# Sheet1.net
KiCad netlist of a schematic drawn in Altium Designer
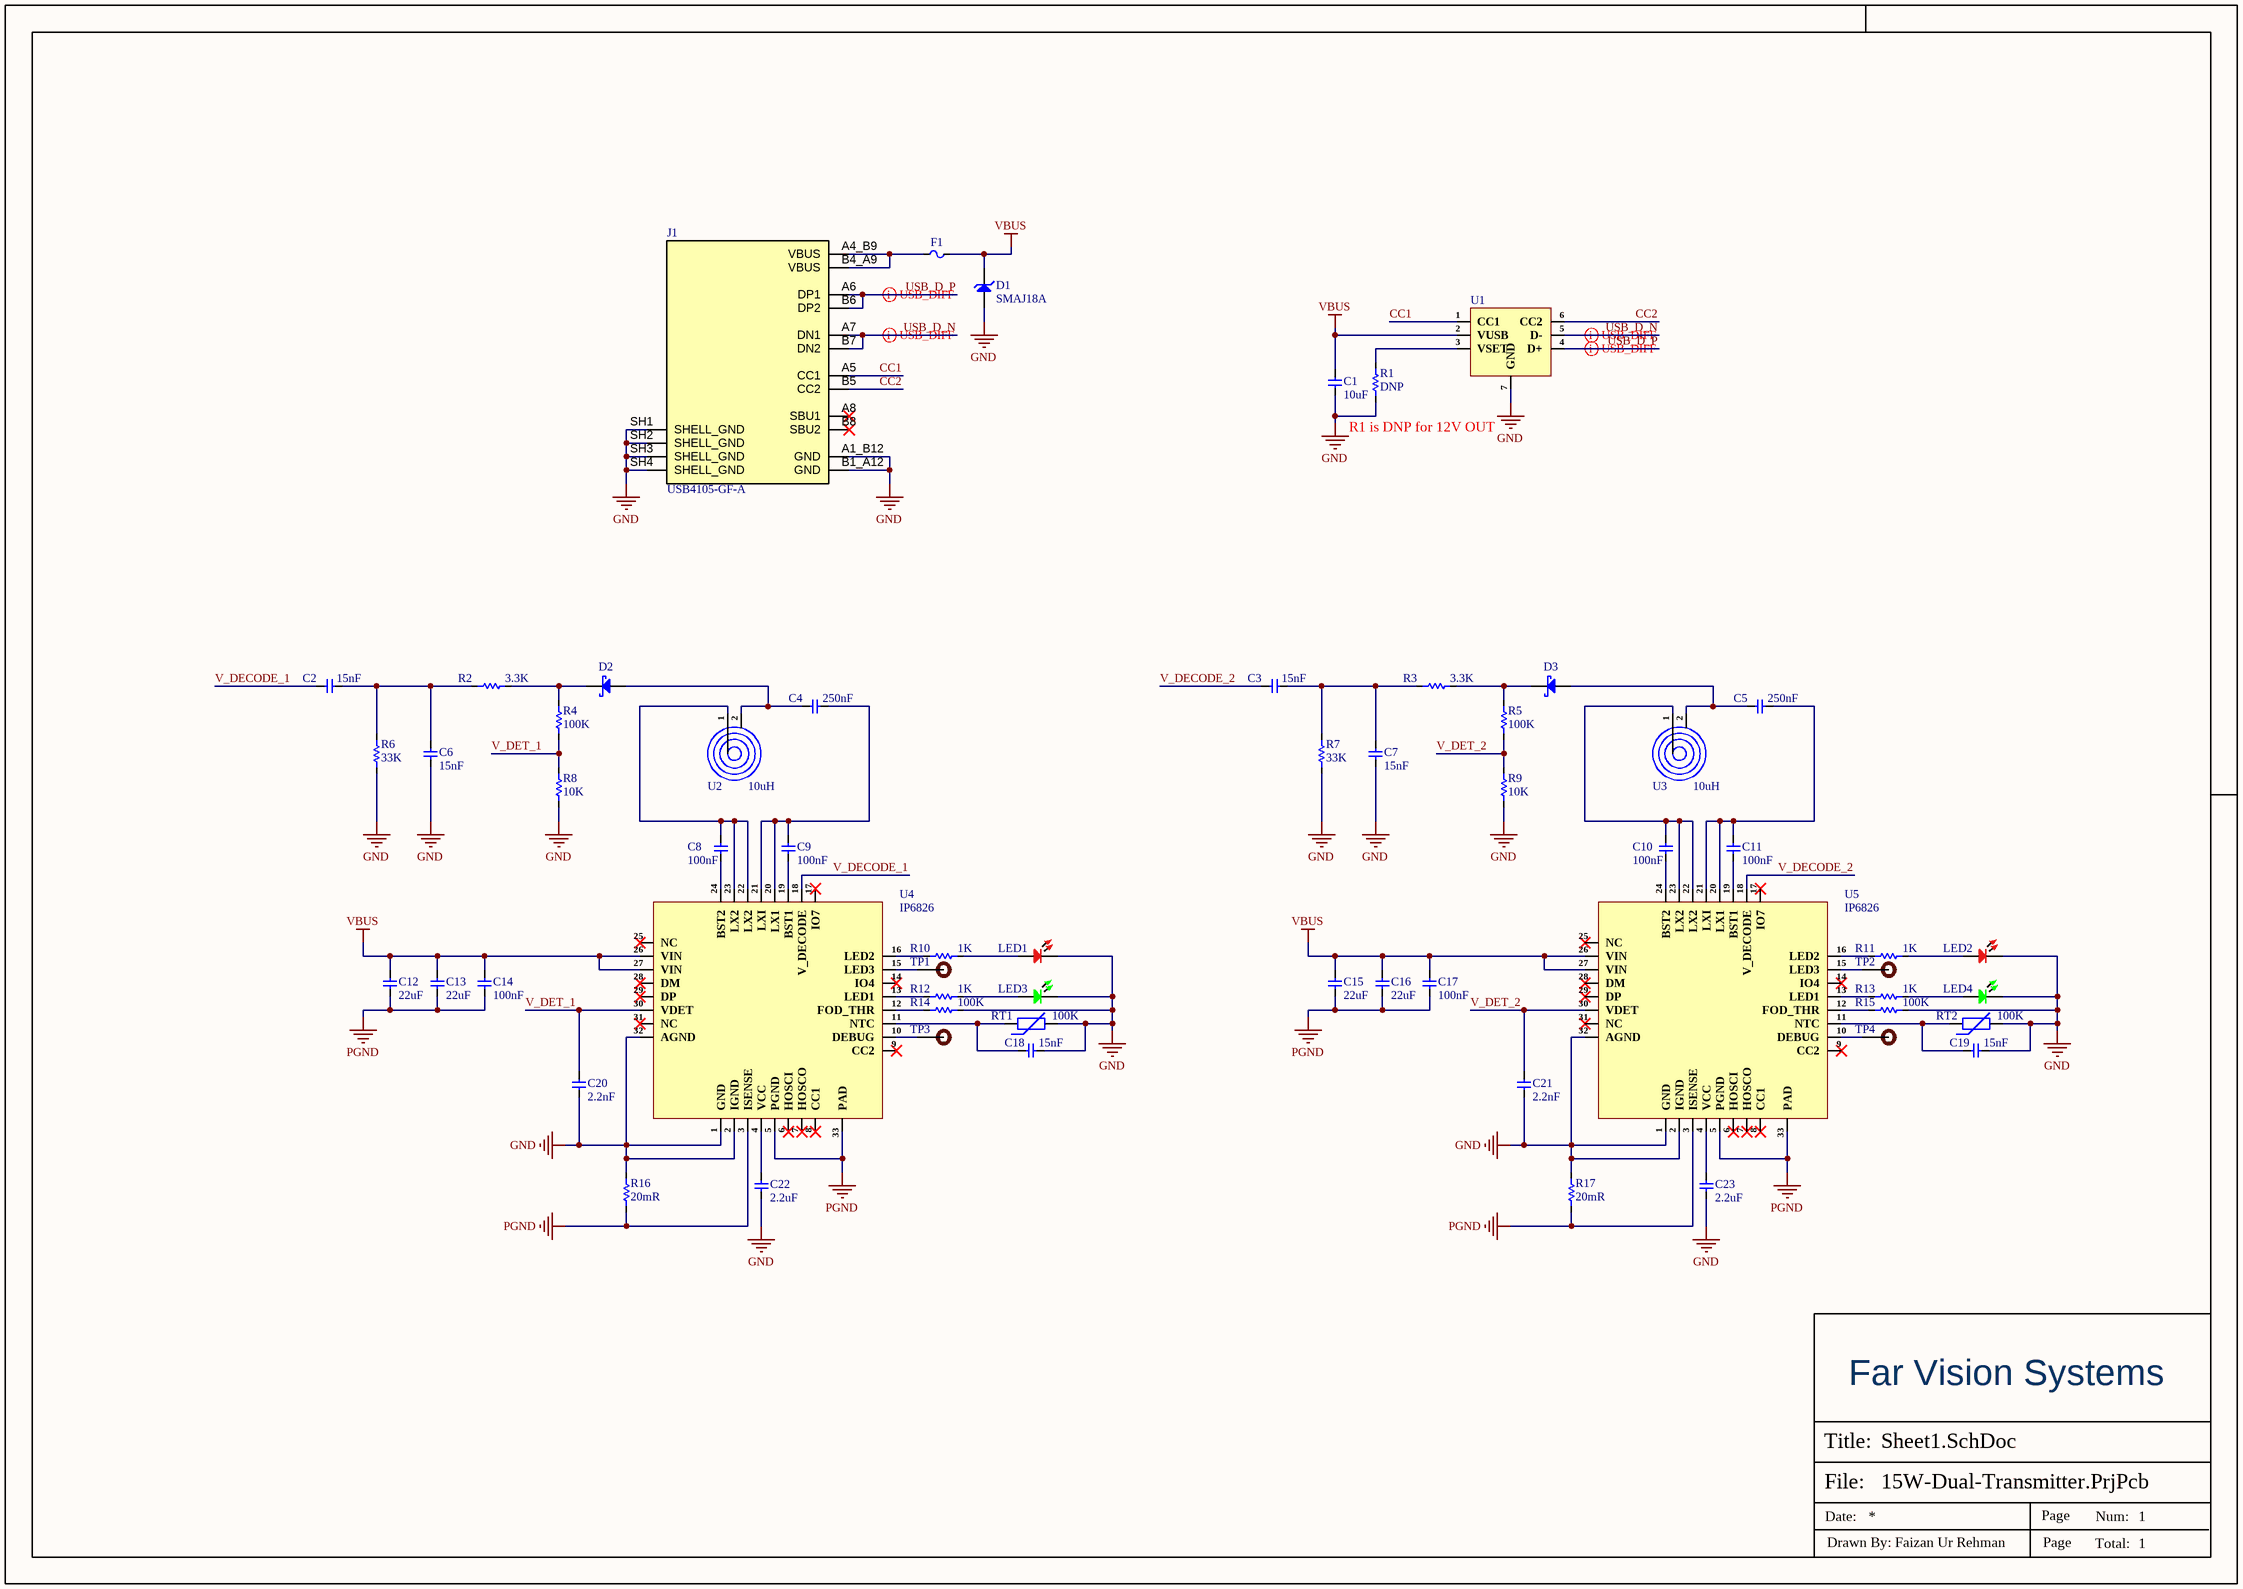
[diagram p0: Sheet1.SchDoc]

(export (version "E")
  (design (tool "Eeschema 10.0.6"))
  (components
    (comp (ref "C1")
      (value "10uF")
      (footprint "Cap-0603")
      (description "GRM188R61E106KA73D")
      (libsource (lib "Schlib1") (part "CAP-0603"))
    )
    (comp (ref "C2")
      (value "15nF")
      (footprint "Cap-0603")
      (description "CC0402KRX7R9BB153")
      (libsource (lib "Schlib1") (part "CAP-0603"))
    )
    (comp (ref "C3")
      (value "15nF")
      (footprint "Cap-0603")
      (description "CC0402KRX7R9BB153")
      (libsource (lib "Schlib1") (part "CAP-0603"))
    )
    (comp (ref "C4")
      (value "250nF")
      (footprint "CAP-TH_L9.0-W3.5-P7.50-D1.0")
      (libsource (lib "Schlib1") (part "MPP254J2A0701"))
    )
    (comp (ref "C5")
      (value "250nF")
      (footprint "CAP-TH_L9.0-W3.5-P7.50-D1.0")
      (libsource (lib "Schlib1") (part "MPP254J2A0701"))
    )
    (comp (ref "C6")
      (value "15nF")
      (footprint "Cap-0603")
      (description "CC0402KRX7R9BB153")
      (libsource (lib "Schlib1") (part "CAP-0603"))
    )
    (comp (ref "C7")
      (value "15nF")
      (footprint "Cap-0603")
      (description "CC0402KRX7R9BB153")
      (libsource (lib "Schlib1") (part "CAP-0603"))
    )
    (comp (ref "C8")
      (value "100nF")
      (footprint "Cap-0603")
      (description "GRM188R71H104KA93D")
      (libsource (lib "Schlib1") (part "CAP-0603"))
    )
    (comp (ref "C9")
      (value "100nF")
      (footprint "Cap-0603")
      (description "GRM188R71H104KA93D")
      (libsource (lib "Schlib1") (part "CAP-0603"))
    )
    (comp (ref "C10")
      (value "100nF")
      (footprint "Cap-0603")
      (description "GRM188R71H104KA93D")
      (libsource (lib "Schlib1") (part "CAP-0603"))
    )
    (comp (ref "C11")
      (value "100nF")
      (footprint "Cap-0603")
      (description "GRM188R71H104KA93D")
      (libsource (lib "Schlib1") (part "CAP-0603"))
    )
    (comp (ref "C12")
      (value "22uF")
      (footprint "Cap-0805")
      (description "CC0805MKX5R8BB226")
      (libsource (lib "Schlib1") (part "CAP-0805"))
    )
    (comp (ref "C13")
      (value "22uF")
      (footprint "Cap-0805")
      (description "CC0805MKX5R8BB226")
      (libsource (lib "Schlib1") (part "CAP-0805"))
    )
    (comp (ref "C14")
      (value "100nF")
      (footprint "Cap-0603")
      (description "GRM188R71H104KA93D")
      (libsource (lib "Schlib1") (part "CAP-0603"))
    )
    (comp (ref "C15")
      (value "22uF")
      (footprint "Cap-0805")
      (description "CC0805MKX5R8BB226")
      (libsource (lib "Schlib1") (part "CAP-0805"))
    )
    (comp (ref "C16")
      (value "22uF")
      (footprint "Cap-0805")
      (description "CC0805MKX5R8BB226")
      (libsource (lib "Schlib1") (part "CAP-0805"))
    )
    (comp (ref "C17")
      (value "100nF")
      (footprint "Cap-0603")
      (description "GRM188R71H104KA93D")
      (libsource (lib "Schlib1") (part "CAP-0603"))
    )
    (comp (ref "C18")
      (value "15nF")
      (footprint "Cap-0603")
      (description "CC0402KRX7R9BB153")
      (libsource (lib "Schlib1") (part "CAP-0603"))
    )
    (comp (ref "C19")
      (value "15nF")
      (footprint "Cap-0603")
      (description "CC0402KRX7R9BB153")
      (libsource (lib "Schlib1") (part "CAP-0603"))
    )
    (comp (ref "C20")
      (value "2.2nF")
      (footprint "Cap-0603")
      (description "GRM188R71H222KA01D")
      (libsource (lib "Schlib1") (part "CAP-0603"))
    )
    (comp (ref "C21")
      (value "2.2nF")
      (footprint "Cap-0603")
      (description "GRM188R71H222KA01D")
      (libsource (lib "Schlib1") (part "CAP-0603"))
    )
    (comp (ref "C22")
      (value "2.2uF")
      (footprint "Cap-0603")
      (description "GRM155R61E225KE11D")
      (libsource (lib "Schlib1") (part "CAP-0603"))
    )
    (comp (ref "C23")
      (value "2.2uF")
      (footprint "Cap-0603")
      (description "GRM155R61E225KE11D")
      (libsource (lib "Schlib1") (part "CAP-0603"))
    )
    (comp (ref "D1")
      (value "SMAJ18A")
      (footprint "SMA(DO-214AC)")
      (fields (field (name "MANUFACTURER") "SMC") (field (name "LCSC PART NUMBER") "C499735"))
      (libsource (lib "Schlib1") (part "SMAJ18A"))
    )
    (comp (ref "D2")
      (value "1N5819HW-7-F")
      (footprint "SOD-123")
      (description "DIODE SCHOTTKY 40V 1A SOD123")
      (fields (field (name "MANUFACTURER") "Diodes") (field (name "LCSC PART NUMBER") "C82544"))
      (libsource (lib "Schlib1") (part "1N5819HW-7-F"))
    )
    (comp (ref "D3")
      (value "1N5819HW-7-F")
      (footprint "SOD-123")
      (description "DIODE SCHOTTKY 40V 1A SOD123")
      (fields (field (name "MANUFACTURER") "Diodes") (field (name "LCSC PART NUMBER") "C82544"))
      (libsource (lib "Schlib1") (part "1N5819HW-7-F"))
    )
    (comp (ref "F1")
      (value "BSMD1812-300-24V")
      (footprint "Fuse-1812_")
      (description "24V 3A 40A 6A 1812 Resettable Fuses ROHS")
      (fields (field (name "LCSC PART NUMBER") "C7500481") (field (name "MANUFACTURER") "BHFUSE"))
      (libsource (lib "Schlib1") (part "BSMD1812-300-24V"))
    )
    (comp (ref "J1")
      (value "USB4105-GF-A")
      (footprint "GCT_USB4105-GF-A")
      (fields (field (name "MF") "{'manufacturer': u'GCT'}"))
      (libsource (lib "Schlib1") (part "USB4105-GF-A"))
    )
    (comp (ref "LED1")
      (value "RED")
      (footprint "LED-0603")
      (description "RED LED 0603 Light Emitting Diodes")
      (fields
        (field (name "MANUFACTURER") "Foshan NationStar Optoelectronics")
        (field (name "MANUFACTURER PART NUMBER") "NCD0603R3")
      )
      (libsource (lib "Schlib1") (part "NCD0603R3"))
    )
    (comp (ref "LED2")
      (value "RED")
      (footprint "LED-0603")
      (description "RED LED 0603 Light Emitting Diodes")
      (fields
        (field (name "MANUFACTURER") "Foshan NationStar Optoelectronics")
        (field (name "MANUFACTURER PART NUMBER") "NCD0603R3")
      )
      (libsource (lib "Schlib1") (part "NCD0603R3"))
    )
    (comp (ref "LED3")
      (value "Emerald")
      (footprint "LED-0603")
      (description "Emerald 0603 Light Emitting Diodes (LED) ROHS")
      (fields
        (field (name "MANUFACTURER") "Foshan NationStar Optoelectronics")
        (field (name "MANUFACTURER PART NUMBER") "NCD0603G2")
      )
      (libsource (lib "Schlib1") (part "NCD0603G2"))
    )
    (comp (ref "LED4")
      (value "Emerald")
      (footprint "LED-0603")
      (description "Emerald 0603 Light Emitting Diodes (LED) ROHS")
      (fields
        (field (name "MANUFACTURER") "Foshan NationStar Optoelectronics")
        (field (name "MANUFACTURER PART NUMBER") "NCD0603G2")
      )
      (libsource (lib "Schlib1") (part "NCD0603G2"))
    )
    (comp (ref "R1") (value "DNP") (footprint "Res-0603") (libsource (lib "Schlib1") (part "RES-0603")))
    (comp (ref "R2")
      (value "3.3K")
      (footprint "Res-0603")
      (description "RC0603FR-073K3L")
      (libsource (lib "Schlib1") (part "RES-0603"))
    )
    (comp (ref "R3")
      (value "3.3K")
      (footprint "Res-0603")
      (description "RC0603FR-073K3L")
      (libsource (lib "Schlib1") (part "RES-0603"))
    )
    (comp (ref "R4")
      (value "100K")
      (footprint "Res-0603")
      (description "RT0603BRD07100KL")
      (libsource (lib "Schlib1") (part "RES-0603"))
    )
    (comp (ref "R5")
      (value "100K")
      (footprint "Res-0603")
      (description "RT0603BRD07100KL")
      (libsource (lib "Schlib1") (part "RES-0603"))
    )
    (comp (ref "R6")
      (value "33K")
      (footprint "Res-0603")
      (description "RC0603FR-0733KL")
      (libsource (lib "Schlib1") (part "RES-0603"))
    )
    (comp (ref "R7")
      (value "33K")
      (footprint "Res-0603")
      (description "RC0603FR-0733KL")
      (libsource (lib "Schlib1") (part "RES-0603"))
    )
    (comp (ref "R8")
      (value "10K")
      (footprint "Res-0603")
      (description "RC0603FR-0710KL")
      (libsource (lib "Schlib1") (part "RES-0603"))
    )
    (comp (ref "R9")
      (value "10K")
      (footprint "Res-0603")
      (description "RC0603FR-0710KL")
      (libsource (lib "Schlib1") (part "RES-0603"))
    )
    (comp (ref "R10")
      (value "1K")
      (footprint "Res-0603")
      (description "RC0603FR-071KL")
      (libsource (lib "Schlib1") (part "RES-0603"))
    )
    (comp (ref "R11")
      (value "1K")
      (footprint "Res-0603")
      (description "RC0603FR-071KL")
      (libsource (lib "Schlib1") (part "RES-0603"))
    )
    (comp (ref "R12") (value "1K") (footprint "Res-0603") (libsource (lib "Schlib1") (part "RES-0603")))
    (comp (ref "R13") (value "1K") (footprint "Res-0603") (libsource (lib "Schlib1") (part "RES-0603")))
    (comp (ref "R14")
      (value "100K")
      (footprint "Res-0603")
      (description "RT0603BRD07100KL")
      (libsource (lib "Schlib1") (part "RES-0603"))
    )
    (comp (ref "R15")
      (value "100K")
      (footprint "Res-0603")
      (description "RT0603BRD07100KL")
      (libsource (lib "Schlib1") (part "RES-0603"))
    )
    (comp (ref "R16")
      (value "20mR")
      (footprint "RES-2512")
      (description "RES 0.02 OHM 1% 2W 2512")
      (fields (field (name "LCSC PART NUMBER") "C375689") (field (name "MANUFACTURER") "Yageo"))
      (libsource (lib "Schlib1") (part "PA2512FKE7W0R02E"))
    )
    (comp (ref "R17")
      (value "20mR")
      (footprint "RES-2512")
      (description "RES 0.02 OHM 1% 2W 2512")
      (fields (field (name "LCSC PART NUMBER") "C375689") (field (name "MANUFACTURER") "Yageo"))
      (libsource (lib "Schlib1") (part "PA2512FKE7W0R02E"))
    )
    (comp (ref "RT1")
      (value "100K")
      (footprint "Res-0603")
      (description "100kΩ 100uA 100mW 3950K ±1% 0603 NTC Thermistors ROHS")
      (fields
        (field (name "MANUFACTURER") "KUU")
        (field (name "MANUFACTURER PART NUMBER") "KNTC0603/100KF3950")
      )
      (libsource (lib "Schlib1") (part "KNTC0603/100KF3950"))
    )
    (comp (ref "RT2")
      (value "100K")
      (footprint "Res-0603")
      (description "100kΩ 100uA 100mW 3950K ±1% 0603 NTC Thermistors ROHS")
      (fields
        (field (name "MANUFACTURER") "KUU")
        (field (name "MANUFACTURER PART NUMBER") "KNTC0603/100KF3950")
      )
      (libsource (lib "Schlib1") (part "KNTC0603/100KF3950"))
    )
    (comp (ref "TP1")
      (value "TEST POINT")
      (footprint "Test-point")
      (description "Test Point ON")
      (libsource (lib "Schlib1") (part "TEST POINT"))
    )
    (comp (ref "TP2")
      (value "TEST POINT")
      (footprint "Test-point")
      (description "Test Point ON")
      (libsource (lib "Schlib1") (part "TEST POINT"))
    )
    (comp (ref "TP3")
      (value "TEST POINT")
      (footprint "Test-point")
      (description "Test Point ON")
      (libsource (lib "Schlib1") (part "TEST POINT"))
    )
    (comp (ref "TP4")
      (value "TEST POINT")
      (footprint "Test-point")
      (description "Test Point ON")
      (libsource (lib "Schlib1") (part "TEST POINT"))
    )
    (comp (ref "U1")
      (value "HUSB237-AA001-DN06R")
      (footprint "DFN-6L-EP(2x2)")
      (description "DFN-6L-EP(2x2) USB PD ROHS")
      (fields (field (name "MANUFACTURER") "Hynetek") (field (name "LCSC PART NUMBER") "C22373734"))
      (libsource (lib "Schlib1") (part "HUSB237-AA001-DN06R"))
    )
    (comp (ref "U2")
      (value "10uH")
      (footprint "760308103102")
      (description "WE-WPCC Wireless Power Transfer Transmitter Coil, THT, Qi - MP-A2, 10uH, 150W")
      (fields
        (field (name "MANUFACTURER PART NUMBER") "760308103102")
        (field (name "MANUFACTURER") "Wurth Elektronik")
      )
      (libsource (lib "Schlib1") (part "760308103102"))
    )
    (comp (ref "U3")
      (value "10uH")
      (footprint "760308103102")
      (description "WE-WPCC Wireless Power Transfer Transmitter Coil, THT, Qi - MP-A2, 10uH, 150W")
      (fields
        (field (name "MANUFACTURER PART NUMBER") "760308103102")
        (field (name "MANUFACTURER") "Wurth Elektronik")
      )
      (libsource (lib "Schlib1") (part "760308103102"))
    )
    (comp (ref "U4")
      (value "IP6826")
      (footprint "QFN-32_L5.0-W5.0-P0.50-BL-EP3.8")
      (libsource (lib "Schlib1") (part "IP6826"))
    )
    (comp (ref "U5")
      (value "IP6826")
      (footprint "QFN-32_L5.0-W5.0-P0.50-BL-EP3.8")
      (libsource (lib "Schlib1") (part "IP6826"))
    )
  )
  (nets
    (net (code "1") (name "/CC1") (class "Default")
      (node (ref "J1") (pin "A5") (pinfunction "CC1_A5") (pintype "passive"))
      (node (ref "U1") (pin "1") (pinfunction "CC1_1") (pintype "passive"))
    )
    (net (code "2") (name "/CC2") (class "Default")
      (node (ref "J1") (pin "B5") (pinfunction "CC2_B5") (pintype "passive"))
      (node (ref "U1") (pin "6") (pinfunction "CC2_6") (pintype "passive"))
    )
    (net (code "3") (name "/USB_D_N") (class "Default")
      (node (ref "J1") (pin "A7") (pinfunction "DN1_A7") (pintype "passive"))
      (node (ref "J1") (pin "B7") (pinfunction "DN2_B7") (pintype "passive"))
      (node (ref "U1") (pin "5") (pinfunction "D-_5") (pintype "passive"))
    )
    (net (code "4") (name "/USB_D_P") (class "Default")
      (node (ref "J1") (pin "A6") (pinfunction "DP1_A6") (pintype "passive"))
      (node (ref "J1") (pin "B6") (pinfunction "DP2_B6") (pintype "passive"))
      (node (ref "U1") (pin "4") (pinfunction "D+_4") (pintype "passive"))
    )
    (net (code "5") (name "/V_DECODE_1") (class "Default")
      (node (ref "C2") (pin "2") (pinfunction "2_2") (pintype "passive"))
      (node (ref "U4") (pin "18") (pinfunction "V_DECODE_18") (pintype "passive"))
    )
    (net (code "6") (name "/V_DECODE_2") (class "Default")
      (node (ref "C3") (pin "2") (pinfunction "2_2") (pintype "passive"))
      (node (ref "U5") (pin "18") (pinfunction "V_DECODE_18") (pintype "passive"))
    )
    (net (code "7") (name "/V_DET_1") (class "Default")
      (node (ref "C20") (pin "2") (pinfunction "2_2") (pintype "passive"))
      (node (ref "R4") (pin "1") (pinfunction "1_1") (pintype "passive"))
      (node (ref "R8") (pin "2") (pinfunction "2_2") (pintype "passive"))
      (node (ref "U4") (pin "30") (pinfunction "VDET_30") (pintype "passive"))
    )
    (net (code "8") (name "/V_DET_2") (class "Default")
      (node (ref "C21") (pin "2") (pinfunction "2_2") (pintype "passive"))
      (node (ref "R5") (pin "1") (pinfunction "1_1") (pintype "passive"))
      (node (ref "R9") (pin "2") (pinfunction "2_2") (pintype "passive"))
      (node (ref "U5") (pin "30") (pinfunction "VDET_30") (pintype "passive"))
    )
    (net (code "9") (name "GND") (class "Default")
      (node (ref "C1") (pin "1") (pinfunction "1_1") (pintype "passive"))
      (node (ref "C18") (pin "2") (pinfunction "2_2") (pintype "passive"))
      (node (ref "C19") (pin "2") (pinfunction "2_2") (pintype "passive"))
      (node (ref "C20") (pin "1") (pinfunction "1_1") (pintype "passive"))
      (node (ref "C21") (pin "1") (pinfunction "1_1") (pintype "passive"))
      (node (ref "C22") (pin "1") (pinfunction "1_1") (pintype "passive"))
      (node (ref "C23") (pin "1") (pinfunction "1_1") (pintype "passive"))
      (node (ref "C6") (pin "1") (pinfunction "1_1") (pintype "passive"))
      (node (ref "C7") (pin "1") (pinfunction "1_1") (pintype "passive"))
      (node (ref "D1") (pin "2") (pinfunction "A_2") (pintype "passive"))
      (node (ref "J1") (pin "A1_B12") (pinfunction "GND_A1_B12") (pintype "passive"))
      (node (ref "J1") (pin "B1_A12") (pinfunction "GND_B1_A12") (pintype "passive"))
      (node (ref "J1") (pin "SH1") (pinfunction "SHELL_GND_SH1") (pintype "passive"))
      (node (ref "J1") (pin "SH2") (pinfunction "SHELL_GND_SH2") (pintype "passive"))
      (node (ref "J1") (pin "SH3") (pinfunction "SHELL_GND_SH3") (pintype "passive"))
      (node (ref "J1") (pin "SH4") (pinfunction "SHELL_GND_SH4") (pintype "passive"))
      (node (ref "LED1") (pin "2") (pinfunction "2_2") (pintype "passive"))
      (node (ref "LED2") (pin "2") (pinfunction "2_2") (pintype "passive"))
      (node (ref "LED3") (pin "2") (pinfunction "2_2") (pintype "passive"))
      (node (ref "LED4") (pin "2") (pinfunction "2_2") (pintype "passive"))
      (node (ref "R1") (pin "1") (pinfunction "1_1") (pintype "passive"))
      (node (ref "R14") (pin "2") (pinfunction "2_2") (pintype "passive"))
      (node (ref "R15") (pin "2") (pinfunction "2_2") (pintype "passive"))
      (node (ref "R16") (pin "2") (pinfunction "2_2") (pintype "passive"))
      (node (ref "R17") (pin "2") (pinfunction "2_2") (pintype "passive"))
      (node (ref "R6") (pin "1") (pinfunction "1_1") (pintype "passive"))
      (node (ref "R7") (pin "1") (pinfunction "1_1") (pintype "passive"))
      (node (ref "R8") (pin "1") (pinfunction "1_1") (pintype "passive"))
      (node (ref "R9") (pin "1") (pinfunction "1_1") (pintype "passive"))
      (node (ref "RT1") (pin "2") (pinfunction "2_2") (pintype "passive"))
      (node (ref "RT2") (pin "2") (pinfunction "2_2") (pintype "passive"))
      (node (ref "U1") (pin "7") (pinfunction "GND_7") (pintype "passive"))
      (node (ref "U4") (pin "1") (pinfunction "GND_1") (pintype "passive"))
      (node (ref "U4") (pin "2") (pinfunction "IGND_2") (pintype "passive"))
      (node (ref "U4") (pin "32") (pinfunction "AGND_32") (pintype "passive"))
      (node (ref "U5") (pin "1") (pinfunction "GND_1") (pintype "passive"))
      (node (ref "U5") (pin "2") (pinfunction "IGND_2") (pintype "passive"))
      (node (ref "U5") (pin "32") (pinfunction "AGND_32") (pintype "passive"))
    )
    (net (code "10") (name "Net-(C2-Pad1)") (class "Default")
      (node (ref "C2") (pin "1") (pinfunction "1_1") (pintype "passive"))
      (node (ref "C6") (pin "2") (pinfunction "2_2") (pintype "passive"))
      (node (ref "R2") (pin "1") (pinfunction "1_1") (pintype "passive"))
      (node (ref "R6") (pin "2") (pinfunction "2_2") (pintype "passive"))
    )
    (net (code "11") (name "Net-(C3-Pad1)") (class "Default")
      (node (ref "C3") (pin "1") (pinfunction "1_1") (pintype "passive"))
      (node (ref "C7") (pin "2") (pinfunction "2_2") (pintype "passive"))
      (node (ref "R3") (pin "1") (pinfunction "1_1") (pintype "passive"))
      (node (ref "R7") (pin "2") (pinfunction "2_2") (pintype "passive"))
    )
    (net (code "12") (name "Net-(C8-Pad2)") (class "Default")
      (node (ref "C8") (pin "2") (pinfunction "2_2") (pintype "passive"))
      (node (ref "U2") (pin "1") (pinfunction "1_1") (pintype "passive"))
      (node (ref "U4") (pin "22") (pinfunction "LX2_22") (pintype "passive"))
      (node (ref "U4") (pin "23") (pinfunction "LX2_23") (pintype "passive"))
    )
    (net (code "13") (name "Net-(C10-Pad2)") (class "Default")
      (node (ref "C10") (pin "2") (pinfunction "2_2") (pintype "passive"))
      (node (ref "U3") (pin "1") (pinfunction "1_1") (pintype "passive"))
      (node (ref "U5") (pin "22") (pinfunction "LX2_22") (pintype "passive"))
      (node (ref "U5") (pin "23") (pinfunction "LX2_23") (pintype "passive"))
    )
    (net (code "14") (name "Net-(D2-A)") (class "Default")
      (node (ref "C4") (pin "1") (pinfunction "1_1") (pintype "passive"))
      (node (ref "D2") (pin "1") (pinfunction "A_1") (pintype "passive"))
      (node (ref "U2") (pin "2") (pinfunction "2_2") (pintype "passive"))
    )
    (net (code "15") (name "Net-(D2-K)") (class "Default")
      (node (ref "D2") (pin "2") (pinfunction "K_2") (pintype "passive"))
      (node (ref "R2") (pin "2") (pinfunction "2_2") (pintype "passive"))
      (node (ref "R4") (pin "2") (pinfunction "2_2") (pintype "passive"))
    )
    (net (code "16") (name "Net-(D3-A)") (class "Default")
      (node (ref "C5") (pin "1") (pinfunction "1_1") (pintype "passive"))
      (node (ref "D3") (pin "1") (pinfunction "A_1") (pintype "passive"))
      (node (ref "U3") (pin "2") (pinfunction "2_2") (pintype "passive"))
    )
    (net (code "17") (name "Net-(D3-K)") (class "Default")
      (node (ref "D3") (pin "2") (pinfunction "K_2") (pintype "passive"))
      (node (ref "R3") (pin "2") (pinfunction "2_2") (pintype "passive"))
      (node (ref "R5") (pin "2") (pinfunction "2_2") (pintype "passive"))
    )
    (net (code "18") (name "Net-(F1-Pad1)") (class "Default")
      (node (ref "F1") (pin "1") (pinfunction "1_1") (pintype "passive"))
      (node (ref "J1") (pin "A4_B9") (pinfunction "VBUS_A4_B9") (pintype "passive"))
      (node (ref "J1") (pin "B4_A9") (pinfunction "VBUS_B4_A9") (pintype "passive"))
    )
    (net (code "19") (name "Net-(LED1-Pad1)") (class "Default")
      (node (ref "LED1") (pin "1") (pinfunction "1_1") (pintype "passive"))
      (node (ref "R10") (pin "2") (pinfunction "2_2") (pintype "passive"))
    )
    (net (code "20") (name "Net-(LED2-Pad1)") (class "Default")
      (node (ref "LED2") (pin "1") (pinfunction "1_1") (pintype "passive"))
      (node (ref "R11") (pin "2") (pinfunction "2_2") (pintype "passive"))
    )
    (net (code "21") (name "Net-(LED3-Pad1)") (class "Default")
      (node (ref "LED3") (pin "1") (pinfunction "1_1") (pintype "passive"))
      (node (ref "R12") (pin "2") (pinfunction "2_2") (pintype "passive"))
    )
    (net (code "22") (name "Net-(LED4-Pad1)") (class "Default")
      (node (ref "LED4") (pin "1") (pinfunction "1_1") (pintype "passive"))
      (node (ref "R13") (pin "2") (pinfunction "2_2") (pintype "passive"))
    )
    (net (code "23") (name "Net-(U1-VSET)") (class "Default")
      (node (ref "R1") (pin "2") (pinfunction "2_2") (pintype "passive"))
      (node (ref "U1") (pin "3") (pinfunction "VSET_3") (pintype "passive"))
    )
    (net (code "24") (name "Net-(U4-BST1)") (class "Default")
      (node (ref "C9") (pin "1") (pinfunction "1_1") (pintype "passive"))
      (node (ref "U4") (pin "19") (pinfunction "BST1_19") (pintype "passive"))
    )
    (net (code "25") (name "Net-(U4-BST2)") (class "Default")
      (node (ref "C8") (pin "1") (pinfunction "1_1") (pintype "passive"))
      (node (ref "U4") (pin "24") (pinfunction "BST2_24") (pintype "passive"))
    )
    (net (code "26") (name "Net-(U4-DEBUG)") (class "Default")
      (node (ref "TP3") (pin "1") (pinfunction "1_1") (pintype "passive"))
      (node (ref "U4") (pin "10") (pinfunction "DEBUG_10") (pintype "passive"))
    )
    (net (code "27") (name "Net-(U4-FOD_THR)") (class "Default")
      (node (ref "R14") (pin "1") (pinfunction "1_1") (pintype "passive"))
      (node (ref "U4") (pin "12") (pinfunction "FOD_THR_12") (pintype "passive"))
    )
    (net (code "28") (name "Net-(U4-LED1)") (class "Default")
      (node (ref "R12") (pin "1") (pinfunction "1_1") (pintype "passive"))
      (node (ref "U4") (pin "13") (pinfunction "LED1_13") (pintype "passive"))
    )
    (net (code "29") (name "Net-(U4-LED2)") (class "Default")
      (node (ref "R10") (pin "1") (pinfunction "1_1") (pintype "passive"))
      (node (ref "U4") (pin "16") (pinfunction "LED2_16") (pintype "passive"))
    )
    (net (code "30") (name "Net-(U4-LED3)") (class "Default")
      (node (ref "TP1") (pin "1") (pinfunction "1_1") (pintype "passive"))
      (node (ref "U4") (pin "15") (pinfunction "LED3_15") (pintype "passive"))
    )
    (net (code "31") (name "Net-(U4-LX1)") (class "Default")
      (node (ref "C4") (pin "2") (pinfunction "2_2") (pintype "passive"))
      (node (ref "C9") (pin "2") (pinfunction "2_2") (pintype "passive"))
      (node (ref "U4") (pin "20") (pinfunction "LX1_20") (pintype "passive"))
      (node (ref "U4") (pin "21") (pinfunction "LXI_21") (pintype "passive"))
    )
    (net (code "32") (name "Net-(U4-NTC)") (class "Default")
      (node (ref "C18") (pin "1") (pinfunction "1_1") (pintype "passive"))
      (node (ref "RT1") (pin "1") (pinfunction "1_1") (pintype "passive"))
      (node (ref "U4") (pin "11") (pinfunction "NTC_11") (pintype "passive"))
    )
    (net (code "33") (name "Net-(U4-VCC)") (class "Default")
      (node (ref "C22") (pin "2") (pinfunction "2_2") (pintype "passive"))
      (node (ref "U4") (pin "4") (pinfunction "VCC_4") (pintype "passive"))
    )
    (net (code "34") (name "Net-(U5-BST1)") (class "Default")
      (node (ref "C11") (pin "1") (pinfunction "1_1") (pintype "passive"))
      (node (ref "U5") (pin "19") (pinfunction "BST1_19") (pintype "passive"))
    )
    (net (code "35") (name "Net-(U5-BST2)") (class "Default")
      (node (ref "C10") (pin "1") (pinfunction "1_1") (pintype "passive"))
      (node (ref "U5") (pin "24") (pinfunction "BST2_24") (pintype "passive"))
    )
    (net (code "36") (name "Net-(U5-DEBUG)") (class "Default")
      (node (ref "TP4") (pin "1") (pinfunction "1_1") (pintype "passive"))
      (node (ref "U5") (pin "10") (pinfunction "DEBUG_10") (pintype "passive"))
    )
    (net (code "37") (name "Net-(U5-FOD_THR)") (class "Default")
      (node (ref "R15") (pin "1") (pinfunction "1_1") (pintype "passive"))
      (node (ref "U5") (pin "12") (pinfunction "FOD_THR_12") (pintype "passive"))
    )
    (net (code "38") (name "Net-(U5-LED1)") (class "Default")
      (node (ref "R13") (pin "1") (pinfunction "1_1") (pintype "passive"))
      (node (ref "U5") (pin "13") (pinfunction "LED1_13") (pintype "passive"))
    )
    (net (code "39") (name "Net-(U5-LED2)") (class "Default")
      (node (ref "R11") (pin "1") (pinfunction "1_1") (pintype "passive"))
      (node (ref "U5") (pin "16") (pinfunction "LED2_16") (pintype "passive"))
    )
    (net (code "40") (name "Net-(U5-LED3)") (class "Default")
      (node (ref "TP2") (pin "1") (pinfunction "1_1") (pintype "passive"))
      (node (ref "U5") (pin "15") (pinfunction "LED3_15") (pintype "passive"))
    )
    (net (code "41") (name "Net-(U5-LX1)") (class "Default")
      (node (ref "C11") (pin "2") (pinfunction "2_2") (pintype "passive"))
      (node (ref "C5") (pin "2") (pinfunction "2_2") (pintype "passive"))
      (node (ref "U5") (pin "20") (pinfunction "LX1_20") (pintype "passive"))
      (node (ref "U5") (pin "21") (pinfunction "LXI_21") (pintype "passive"))
    )
    (net (code "42") (name "Net-(U5-NTC)") (class "Default")
      (node (ref "C19") (pin "1") (pinfunction "1_1") (pintype "passive"))
      (node (ref "RT2") (pin "1") (pinfunction "1_1") (pintype "passive"))
      (node (ref "U5") (pin "11") (pinfunction "NTC_11") (pintype "passive"))
    )
    (net (code "43") (name "Net-(U5-VCC)") (class "Default")
      (node (ref "C23") (pin "2") (pinfunction "2_2") (pintype "passive"))
      (node (ref "U5") (pin "4") (pinfunction "VCC_4") (pintype "passive"))
    )
    (net (code "44") (name "PGND") (class "Default")
      (node (ref "C12") (pin "1") (pinfunction "1_1") (pintype "passive"))
      (node (ref "C13") (pin "1") (pinfunction "1_1") (pintype "passive"))
      (node (ref "C14") (pin "1") (pinfunction "1_1") (pintype "passive"))
      (node (ref "C15") (pin "1") (pinfunction "1_1") (pintype "passive"))
      (node (ref "C16") (pin "1") (pinfunction "1_1") (pintype "passive"))
      (node (ref "C17") (pin "1") (pinfunction "1_1") (pintype "passive"))
      (node (ref "R16") (pin "1") (pinfunction "1_1") (pintype "passive"))
      (node (ref "R17") (pin "1") (pinfunction "1_1") (pintype "passive"))
      (node (ref "U4") (pin "3") (pinfunction "ISENSE_3") (pintype "passive"))
      (node (ref "U4") (pin "33") (pinfunction "PAD_33") (pintype "passive"))
      (node (ref "U4") (pin "5") (pinfunction "PGND_5") (pintype "passive"))
      (node (ref "U5") (pin "3") (pinfunction "ISENSE_3") (pintype "passive"))
      (node (ref "U5") (pin "33") (pinfunction "PAD_33") (pintype "passive"))
      (node (ref "U5") (pin "5") (pinfunction "PGND_5") (pintype "passive"))
    )
    (net (code "45") (name "VBUS") (class "Default")
      (node (ref "C1") (pin "2") (pinfunction "2_2") (pintype "passive"))
      (node (ref "C12") (pin "2") (pinfunction "2_2") (pintype "passive"))
      (node (ref "C13") (pin "2") (pinfunction "2_2") (pintype "passive"))
      (node (ref "C14") (pin "2") (pinfunction "2_2") (pintype "passive"))
      (node (ref "C15") (pin "2") (pinfunction "2_2") (pintype "passive"))
      (node (ref "C16") (pin "2") (pinfunction "2_2") (pintype "passive"))
      (node (ref "C17") (pin "2") (pinfunction "2_2") (pintype "passive"))
      (node (ref "D1") (pin "1") (pinfunction "K_1") (pintype "passive"))
      (node (ref "F1") (pin "2") (pinfunction "2_2") (pintype "passive"))
      (node (ref "U1") (pin "2") (pinfunction "VUSB_2") (pintype "passive"))
      (node (ref "U4") (pin "26") (pinfunction "VIN_26") (pintype "passive"))
      (node (ref "U4") (pin "27") (pinfunction "VIN_27") (pintype "passive"))
      (node (ref "U5") (pin "26") (pinfunction "VIN_26") (pintype "passive"))
      (node (ref "U5") (pin "27") (pinfunction "VIN_27") (pintype "passive"))
    )
    (net (code "46") (name "unconnected-(J1-SBU1-PadA8)") (class "Default")
      (node (ref "J1") (pin "A8") (pinfunction "SBU1_A8") (pintype "passive+no_connect"))
    )
    (net (code "47") (name "unconnected-(J1-SBU2-PadB8)") (class "Default")
      (node (ref "J1") (pin "B8") (pinfunction "SBU2_B8") (pintype "passive+no_connect"))
    )
    (net (code "48") (name "unconnected-(U4-CC1-Pad8)") (class "Default")
      (node (ref "U4") (pin "8") (pinfunction "CC1_8") (pintype "passive+no_connect"))
    )
    (net (code "49") (name "unconnected-(U4-CC2-Pad9)") (class "Default")
      (node (ref "U4") (pin "9") (pinfunction "CC2_9") (pintype "passive+no_connect"))
    )
    (net (code "50") (name "unconnected-(U4-DM-Pad28)") (class "Default")
      (node (ref "U4") (pin "28") (pinfunction "DM_28") (pintype "passive+no_connect"))
    )
    (net (code "51") (name "unconnected-(U4-DP-Pad29)") (class "Default")
      (node (ref "U4") (pin "29") (pinfunction "DP_29") (pintype "passive+no_connect"))
    )
    (net (code "52") (name "unconnected-(U4-HOSCI-Pad6)") (class "Default")
      (node (ref "U4") (pin "6") (pinfunction "HOSCI_6") (pintype "passive+no_connect"))
    )
    (net (code "53") (name "unconnected-(U4-HOSCO-Pad7)") (class "Default")
      (node (ref "U4") (pin "7") (pinfunction "HOSCO_7") (pintype "passive+no_connect"))
    )
    (net (code "54") (name "unconnected-(U4-IO4-Pad14)") (class "Default")
      (node (ref "U4") (pin "14") (pinfunction "IO4_14") (pintype "passive+no_connect"))
    )
    (net (code "55") (name "unconnected-(U4-IO7-Pad17)") (class "Default")
      (node (ref "U4") (pin "17") (pinfunction "IO7_17") (pintype "passive+no_connect"))
    )
    (net (code "56") (name "unconnected-(U4-NC-Pad25)") (class "Default")
      (node (ref "U4") (pin "25") (pinfunction "NC_25") (pintype "passive+no_connect"))
    )
    (net (code "57") (name "unconnected-(U4-NC-Pad31)") (class "Default")
      (node (ref "U4") (pin "31") (pinfunction "NC_31") (pintype "passive+no_connect"))
    )
    (net (code "58") (name "unconnected-(U5-CC1-Pad8)") (class "Default")
      (node (ref "U5") (pin "8") (pinfunction "CC1_8") (pintype "passive+no_connect"))
    )
    (net (code "59") (name "unconnected-(U5-CC2-Pad9)") (class "Default")
      (node (ref "U5") (pin "9") (pinfunction "CC2_9") (pintype "passive+no_connect"))
    )
    (net (code "60") (name "unconnected-(U5-DM-Pad28)") (class "Default")
      (node (ref "U5") (pin "28") (pinfunction "DM_28") (pintype "passive+no_connect"))
    )
    (net (code "61") (name "unconnected-(U5-DP-Pad29)") (class "Default")
      (node (ref "U5") (pin "29") (pinfunction "DP_29") (pintype "passive+no_connect"))
    )
    (net (code "62") (name "unconnected-(U5-HOSCI-Pad6)") (class "Default")
      (node (ref "U5") (pin "6") (pinfunction "HOSCI_6") (pintype "passive+no_connect"))
    )
    (net (code "63") (name "unconnected-(U5-HOSCO-Pad7)") (class "Default")
      (node (ref "U5") (pin "7") (pinfunction "HOSCO_7") (pintype "passive+no_connect"))
    )
    (net (code "64") (name "unconnected-(U5-IO4-Pad14)") (class "Default")
      (node (ref "U5") (pin "14") (pinfunction "IO4_14") (pintype "passive+no_connect"))
    )
    (net (code "65") (name "unconnected-(U5-IO7-Pad17)") (class "Default")
      (node (ref "U5") (pin "17") (pinfunction "IO7_17") (pintype "passive+no_connect"))
    )
    (net (code "66") (name "unconnected-(U5-NC-Pad25)") (class "Default")
      (node (ref "U5") (pin "25") (pinfunction "NC_25") (pintype "passive+no_connect"))
    )
    (net (code "67") (name "unconnected-(U5-NC-Pad31)") (class "Default")
      (node (ref "U5") (pin "31") (pinfunction "NC_31") (pintype "passive+no_connect"))
    )
  )
)
